# FPGA_Power.net
KiCad netlist of a schematic drawn in Altium Designer
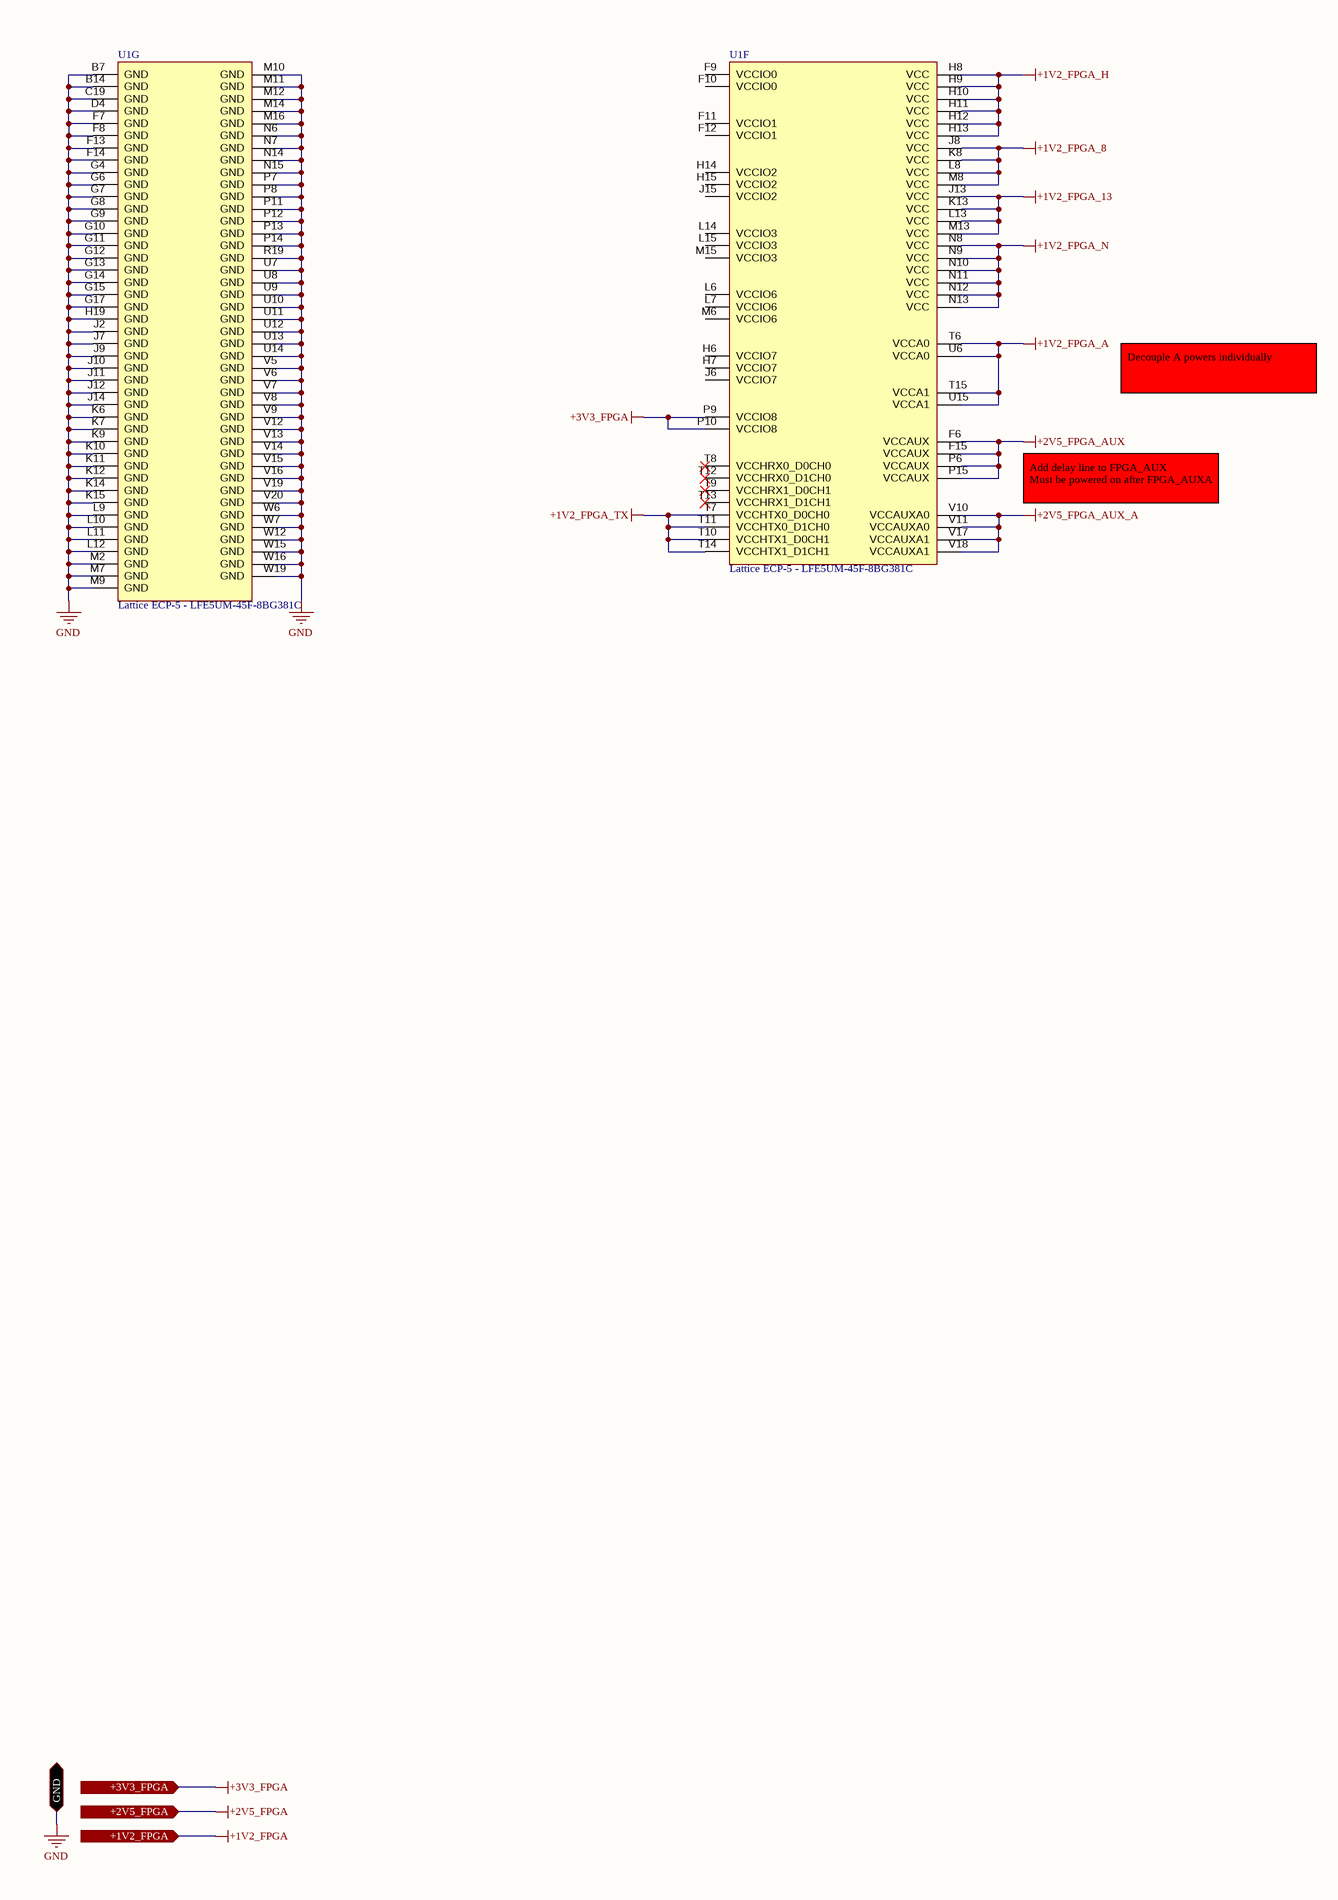
[diagram p0: FPGA Power.SchDoc, left]
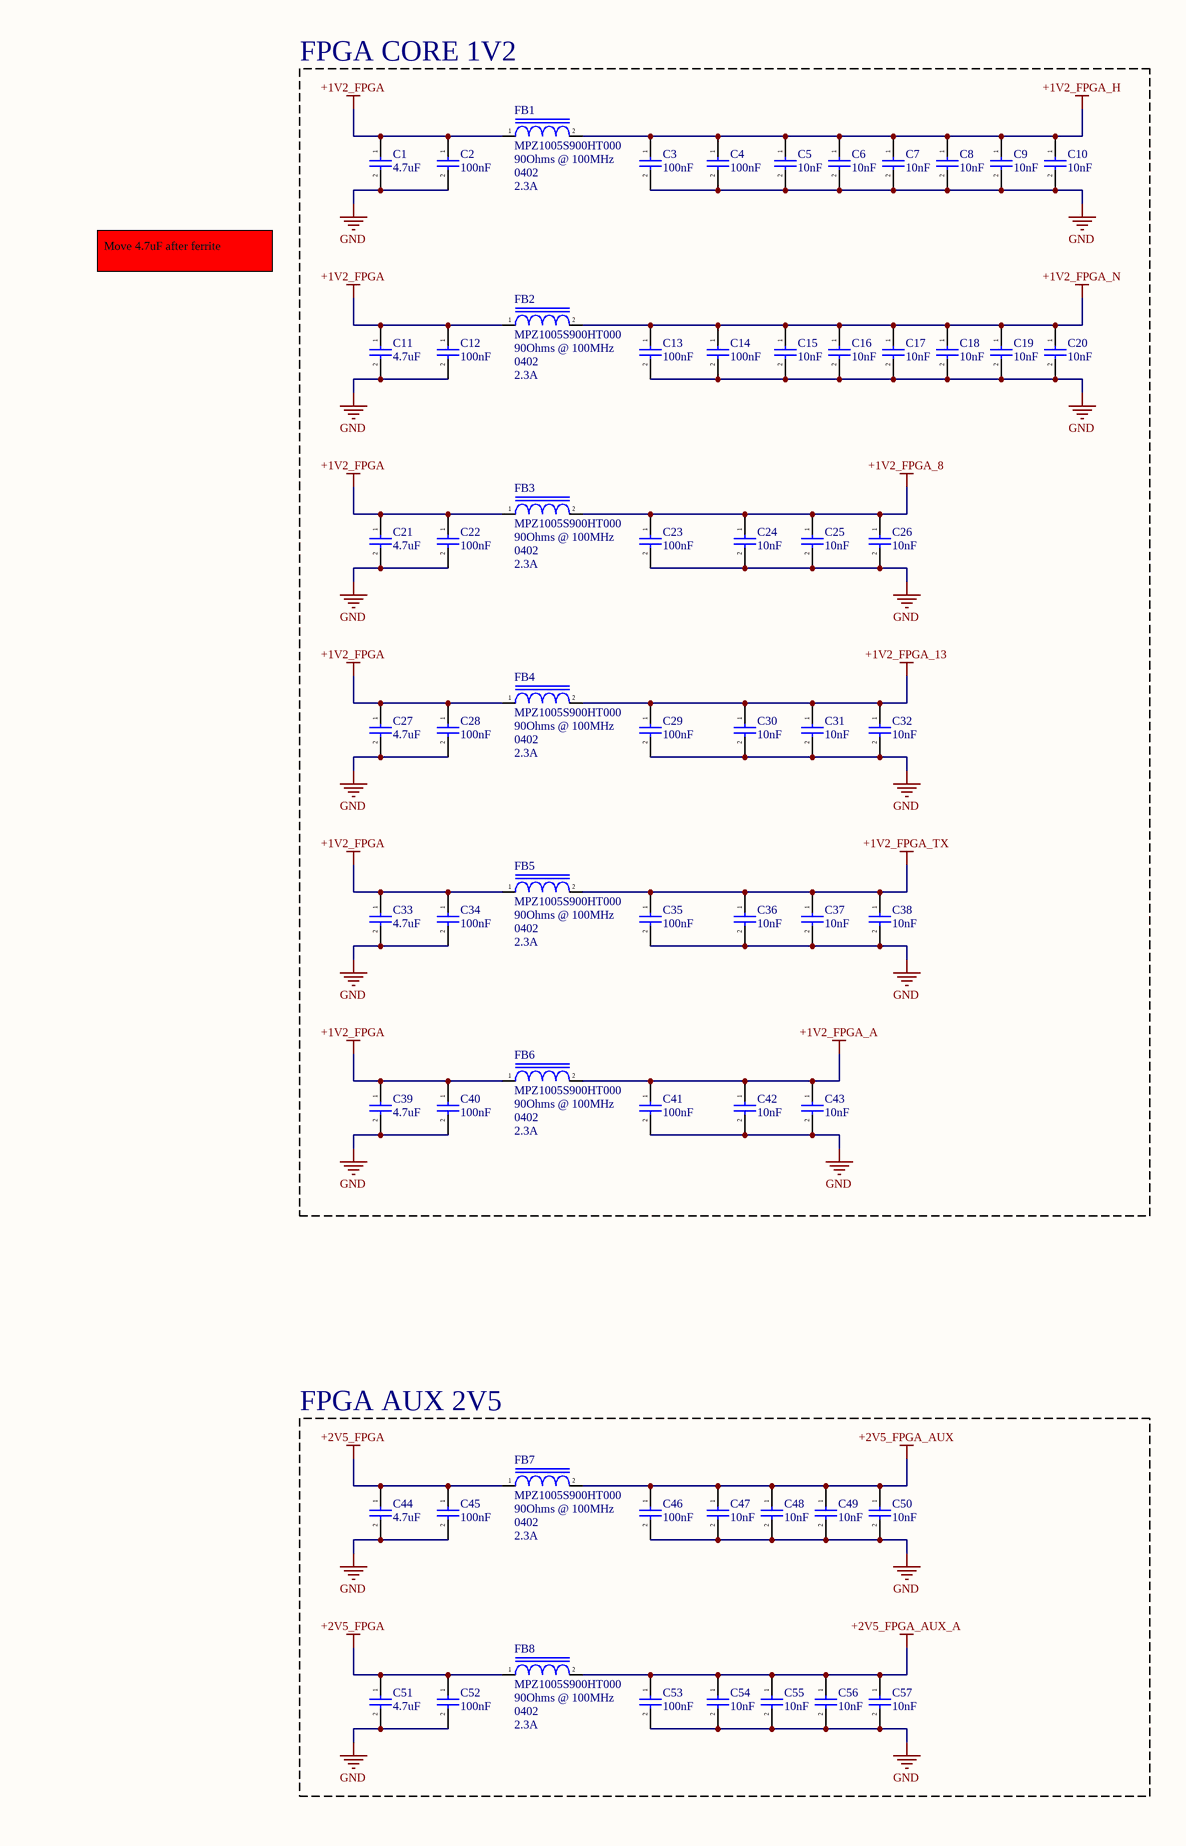
[diagram p1: FPGA Power.SchDoc, right]

(export (version "E")
  (design (tool "Eeschema 10.0.6"))
  (components
    (comp (ref "C1")
      (value "4.7uF")
      (footprint "CAP_0805")
      (description "Generic SMT Ceramic Capacitor")
      (libsource (lib "Symbols") (part "CAP_CER"))
    )
    (comp (ref "C2")
      (value "100nF")
      (footprint "CAP_0402")
      (description "Generic SMT Ceramic Capacitor")
      (libsource (lib "Symbols") (part "CAP_CER"))
    )
    (comp (ref "C3")
      (value "100nF")
      (footprint "CAP_0402")
      (description "Generic SMT Ceramic Capacitor")
      (libsource (lib "Symbols") (part "CAP_CER"))
    )
    (comp (ref "C4")
      (value "100nF")
      (footprint "CAP_0402")
      (description "Generic SMT Ceramic Capacitor")
      (libsource (lib "Symbols") (part "CAP_CER"))
    )
    (comp (ref "C5")
      (value "10nF")
      (footprint "CAP_0201")
      (description "Generic SMT Ceramic Capacitor")
      (libsource (lib "Symbols") (part "CAP_CER"))
    )
    (comp (ref "C6")
      (value "10nF")
      (footprint "CAP_0201")
      (description "Generic SMT Ceramic Capacitor")
      (libsource (lib "Symbols") (part "CAP_CER"))
    )
    (comp (ref "C7")
      (value "10nF")
      (footprint "CAP_0201")
      (description "Generic SMT Ceramic Capacitor")
      (libsource (lib "Symbols") (part "CAP_CER"))
    )
    (comp (ref "C8")
      (value "10nF")
      (footprint "CAP_0201")
      (description "Generic SMT Ceramic Capacitor")
      (libsource (lib "Symbols") (part "CAP_CER"))
    )
    (comp (ref "C9")
      (value "10nF")
      (footprint "CAP_0201")
      (description "Generic SMT Ceramic Capacitor")
      (libsource (lib "Symbols") (part "CAP_CER"))
    )
    (comp (ref "C10")
      (value "10nF")
      (footprint "CAP_0201")
      (description "Generic SMT Ceramic Capacitor")
      (libsource (lib "Symbols") (part "CAP_CER"))
    )
    (comp (ref "C11")
      (value "4.7uF")
      (footprint "CAP_0805")
      (description "Generic SMT Ceramic Capacitor")
      (libsource (lib "Symbols") (part "CAP_CER"))
    )
    (comp (ref "C12")
      (value "100nF")
      (footprint "CAP_0402")
      (description "Generic SMT Ceramic Capacitor")
      (libsource (lib "Symbols") (part "CAP_CER"))
    )
    (comp (ref "C13")
      (value "100nF")
      (footprint "CAP_0402")
      (description "Generic SMT Ceramic Capacitor")
      (libsource (lib "Symbols") (part "CAP_CER"))
    )
    (comp (ref "C14")
      (value "100nF")
      (footprint "CAP_0402")
      (description "Generic SMT Ceramic Capacitor")
      (libsource (lib "Symbols") (part "CAP_CER"))
    )
    (comp (ref "C15")
      (value "10nF")
      (footprint "CAP_0201")
      (description "Generic SMT Ceramic Capacitor")
      (libsource (lib "Symbols") (part "CAP_CER"))
    )
    (comp (ref "C16")
      (value "10nF")
      (footprint "CAP_0201")
      (description "Generic SMT Ceramic Capacitor")
      (libsource (lib "Symbols") (part "CAP_CER"))
    )
    (comp (ref "C17")
      (value "10nF")
      (footprint "CAP_0201")
      (description "Generic SMT Ceramic Capacitor")
      (libsource (lib "Symbols") (part "CAP_CER"))
    )
    (comp (ref "C18")
      (value "10nF")
      (footprint "CAP_0201")
      (description "Generic SMT Ceramic Capacitor")
      (libsource (lib "Symbols") (part "CAP_CER"))
    )
    (comp (ref "C19")
      (value "10nF")
      (footprint "CAP_0201")
      (description "Generic SMT Ceramic Capacitor")
      (libsource (lib "Symbols") (part "CAP_CER"))
    )
    (comp (ref "C20")
      (value "10nF")
      (footprint "CAP_0201")
      (description "Generic SMT Ceramic Capacitor")
      (libsource (lib "Symbols") (part "CAP_CER"))
    )
    (comp (ref "C21")
      (value "4.7uF")
      (footprint "CAP_0805")
      (description "Generic SMT Ceramic Capacitor")
      (libsource (lib "Symbols") (part "CAP_CER"))
    )
    (comp (ref "C22")
      (value "100nF")
      (footprint "CAP_0402")
      (description "Generic SMT Ceramic Capacitor")
      (libsource (lib "Symbols") (part "CAP_CER"))
    )
    (comp (ref "C23")
      (value "100nF")
      (footprint "CAP_0402")
      (description "Generic SMT Ceramic Capacitor")
      (libsource (lib "Symbols") (part "CAP_CER"))
    )
    (comp (ref "C24")
      (value "10nF")
      (footprint "CAP_0201")
      (description "Generic SMT Ceramic Capacitor")
      (libsource (lib "Symbols") (part "CAP_CER"))
    )
    (comp (ref "C25")
      (value "10nF")
      (footprint "CAP_0201")
      (description "Generic SMT Ceramic Capacitor")
      (libsource (lib "Symbols") (part "CAP_CER"))
    )
    (comp (ref "C26")
      (value "10nF")
      (footprint "CAP_0201")
      (description "Generic SMT Ceramic Capacitor")
      (libsource (lib "Symbols") (part "CAP_CER"))
    )
    (comp (ref "C27")
      (value "4.7uF")
      (footprint "CAP_0805")
      (description "Generic SMT Ceramic Capacitor")
      (libsource (lib "Symbols") (part "CAP_CER"))
    )
    (comp (ref "C28")
      (value "100nF")
      (footprint "CAP_0402")
      (description "Generic SMT Ceramic Capacitor")
      (libsource (lib "Symbols") (part "CAP_CER"))
    )
    (comp (ref "C29")
      (value "100nF")
      (footprint "CAP_0402")
      (description "Generic SMT Ceramic Capacitor")
      (libsource (lib "Symbols") (part "CAP_CER"))
    )
    (comp (ref "C30")
      (value "10nF")
      (footprint "CAP_0201")
      (description "Generic SMT Ceramic Capacitor")
      (libsource (lib "Symbols") (part "CAP_CER"))
    )
    (comp (ref "C31")
      (value "10nF")
      (footprint "CAP_0201")
      (description "Generic SMT Ceramic Capacitor")
      (libsource (lib "Symbols") (part "CAP_CER"))
    )
    (comp (ref "C32")
      (value "10nF")
      (footprint "CAP_0201")
      (description "Generic SMT Ceramic Capacitor")
      (libsource (lib "Symbols") (part "CAP_CER"))
    )
    (comp (ref "C33")
      (value "4.7uF")
      (footprint "CAP_0805")
      (description "Generic SMT Ceramic Capacitor")
      (libsource (lib "Symbols") (part "CAP_CER"))
    )
    (comp (ref "C34")
      (value "100nF")
      (footprint "CAP_0402")
      (description "Generic SMT Ceramic Capacitor")
      (libsource (lib "Symbols") (part "CAP_CER"))
    )
    (comp (ref "C35")
      (value "100nF")
      (footprint "CAP_0402")
      (description "Generic SMT Ceramic Capacitor")
      (libsource (lib "Symbols") (part "CAP_CER"))
    )
    (comp (ref "C36")
      (value "10nF")
      (footprint "CAP_0201")
      (description "Generic SMT Ceramic Capacitor")
      (libsource (lib "Symbols") (part "CAP_CER"))
    )
    (comp (ref "C37")
      (value "10nF")
      (footprint "CAP_0201")
      (description "Generic SMT Ceramic Capacitor")
      (libsource (lib "Symbols") (part "CAP_CER"))
    )
    (comp (ref "C38")
      (value "10nF")
      (footprint "CAP_0201")
      (description "Generic SMT Ceramic Capacitor")
      (libsource (lib "Symbols") (part "CAP_CER"))
    )
    (comp (ref "C39")
      (value "4.7uF")
      (footprint "CAP_0805")
      (description "Generic SMT Ceramic Capacitor")
      (libsource (lib "Symbols") (part "CAP_CER"))
    )
    (comp (ref "C40")
      (value "100nF")
      (footprint "CAP_0402")
      (description "Generic SMT Ceramic Capacitor")
      (libsource (lib "Symbols") (part "CAP_CER"))
    )
    (comp (ref "C41")
      (value "100nF")
      (footprint "CAP_0402")
      (description "Generic SMT Ceramic Capacitor")
      (libsource (lib "Symbols") (part "CAP_CER"))
    )
    (comp (ref "C42")
      (value "10nF")
      (footprint "CAP_0201")
      (description "Generic SMT Ceramic Capacitor")
      (libsource (lib "Symbols") (part "CAP_CER"))
    )
    (comp (ref "C43")
      (value "10nF")
      (footprint "CAP_0201")
      (description "Generic SMT Ceramic Capacitor")
      (libsource (lib "Symbols") (part "CAP_CER"))
    )
    (comp (ref "C44")
      (value "4.7uF")
      (footprint "CAP_0805")
      (description "Generic SMT Ceramic Capacitor")
      (libsource (lib "Symbols") (part "CAP_CER"))
    )
    (comp (ref "C45")
      (value "100nF")
      (footprint "CAP_0402")
      (description "Generic SMT Ceramic Capacitor")
      (libsource (lib "Symbols") (part "CAP_CER"))
    )
    (comp (ref "C46")
      (value "100nF")
      (footprint "CAP_0402")
      (description "Generic SMT Ceramic Capacitor")
      (libsource (lib "Symbols") (part "CAP_CER"))
    )
    (comp (ref "C47")
      (value "10nF")
      (footprint "CAP_0201")
      (description "Generic SMT Ceramic Capacitor")
      (libsource (lib "Symbols") (part "CAP_CER"))
    )
    (comp (ref "C48")
      (value "10nF")
      (footprint "CAP_0201")
      (description "Generic SMT Ceramic Capacitor")
      (libsource (lib "Symbols") (part "CAP_CER"))
    )
    (comp (ref "C49")
      (value "10nF")
      (footprint "CAP_0201")
      (description "Generic SMT Ceramic Capacitor")
      (libsource (lib "Symbols") (part "CAP_CER"))
    )
    (comp (ref "C50")
      (value "10nF")
      (footprint "CAP_0201")
      (description "Generic SMT Ceramic Capacitor")
      (libsource (lib "Symbols") (part "CAP_CER"))
    )
    (comp (ref "C51")
      (value "4.7uF")
      (footprint "CAP_0805")
      (description "Generic SMT Ceramic Capacitor")
      (libsource (lib "Symbols") (part "CAP_CER"))
    )
    (comp (ref "C52")
      (value "100nF")
      (footprint "CAP_0402")
      (description "Generic SMT Ceramic Capacitor")
      (libsource (lib "Symbols") (part "CAP_CER"))
    )
    (comp (ref "C53")
      (value "100nF")
      (footprint "CAP_0402")
      (description "Generic SMT Ceramic Capacitor")
      (libsource (lib "Symbols") (part "CAP_CER"))
    )
    (comp (ref "C54")
      (value "10nF")
      (footprint "CAP_0201")
      (description "Generic SMT Ceramic Capacitor")
      (libsource (lib "Symbols") (part "CAP_CER"))
    )
    (comp (ref "C55")
      (value "10nF")
      (footprint "CAP_0201")
      (description "Generic SMT Ceramic Capacitor")
      (libsource (lib "Symbols") (part "CAP_CER"))
    )
    (comp (ref "C56")
      (value "10nF")
      (footprint "CAP_0201")
      (description "Generic SMT Ceramic Capacitor")
      (libsource (lib "Symbols") (part "CAP_CER"))
    )
    (comp (ref "C57")
      (value "10nF")
      (footprint "CAP_0201")
      (description "Generic SMT Ceramic Capacitor")
      (libsource (lib "Symbols") (part "CAP_CER"))
    )
    (comp (ref "FB1")
      (value "MPZ1005S900HT000")
      (footprint "IND_0402")
      (description "90 Ohms @ 100 MHz 1 Power Line Ferrite Bead 0402 (1005 Metric) 2.3A 38mOhm")
      (fields
        (field (name "IMPEDANCE @ FREQ") "90Ohms @ 100MHz")
        (field (name "PACKAGE / CASE") "0402")
        (field (name "CURRENT RATING") "2.3A")
      )
      (libsource (lib "CryptLib") (part "IND_MPZ1005S900HT000"))
    )
    (comp (ref "FB2")
      (value "MPZ1005S900HT000")
      (footprint "IND_0402")
      (description "90 Ohms @ 100 MHz 1 Power Line Ferrite Bead 0402 (1005 Metric) 2.3A 38mOhm")
      (fields
        (field (name "IMPEDANCE @ FREQ") "90Ohms @ 100MHz")
        (field (name "PACKAGE / CASE") "0402")
        (field (name "CURRENT RATING") "2.3A")
      )
      (libsource (lib "CryptLib") (part "IND_MPZ1005S900HT000"))
    )
    (comp (ref "FB3")
      (value "MPZ1005S900HT000")
      (footprint "IND_0402")
      (description "90 Ohms @ 100 MHz 1 Power Line Ferrite Bead 0402 (1005 Metric) 2.3A 38mOhm")
      (fields
        (field (name "IMPEDANCE @ FREQ") "90Ohms @ 100MHz")
        (field (name "PACKAGE / CASE") "0402")
        (field (name "CURRENT RATING") "2.3A")
      )
      (libsource (lib "CryptLib") (part "IND_MPZ1005S900HT000"))
    )
    (comp (ref "FB4")
      (value "MPZ1005S900HT000")
      (footprint "IND_0402")
      (description "90 Ohms @ 100 MHz 1 Power Line Ferrite Bead 0402 (1005 Metric) 2.3A 38mOhm")
      (fields
        (field (name "IMPEDANCE @ FREQ") "90Ohms @ 100MHz")
        (field (name "PACKAGE / CASE") "0402")
        (field (name "CURRENT RATING") "2.3A")
      )
      (libsource (lib "CryptLib") (part "IND_MPZ1005S900HT000"))
    )
    (comp (ref "FB5")
      (value "MPZ1005S900HT000")
      (footprint "IND_0402")
      (description "90 Ohms @ 100 MHz 1 Power Line Ferrite Bead 0402 (1005 Metric) 2.3A 38mOhm")
      (fields
        (field (name "IMPEDANCE @ FREQ") "90Ohms @ 100MHz")
        (field (name "PACKAGE / CASE") "0402")
        (field (name "CURRENT RATING") "2.3A")
      )
      (libsource (lib "CryptLib") (part "IND_MPZ1005S900HT000"))
    )
    (comp (ref "FB6")
      (value "MPZ1005S900HT000")
      (footprint "IND_0402")
      (description "90 Ohms @ 100 MHz 1 Power Line Ferrite Bead 0402 (1005 Metric) 2.3A 38mOhm")
      (fields
        (field (name "IMPEDANCE @ FREQ") "90Ohms @ 100MHz")
        (field (name "PACKAGE / CASE") "0402")
        (field (name "CURRENT RATING") "2.3A")
      )
      (libsource (lib "CryptLib") (part "IND_MPZ1005S900HT000"))
    )
    (comp (ref "FB7")
      (value "MPZ1005S900HT000")
      (footprint "IND_0402")
      (description "90 Ohms @ 100 MHz 1 Power Line Ferrite Bead 0402 (1005 Metric) 2.3A 38mOhm")
      (fields
        (field (name "IMPEDANCE @ FREQ") "90Ohms @ 100MHz")
        (field (name "PACKAGE / CASE") "0402")
        (field (name "CURRENT RATING") "2.3A")
      )
      (libsource (lib "CryptLib") (part "IND_MPZ1005S900HT000"))
    )
    (comp (ref "FB8")
      (value "MPZ1005S900HT000")
      (footprint "IND_0402")
      (description "90 Ohms @ 100 MHz 1 Power Line Ferrite Bead 0402 (1005 Metric) 2.3A 38mOhm")
      (fields
        (field (name "IMPEDANCE @ FREQ") "90Ohms @ 100MHz")
        (field (name "PACKAGE / CASE") "0402")
        (field (name "CURRENT RATING") "2.3A")
      )
      (libsource (lib "CryptLib") (part "IND_MPZ1005S900HT000"))
    )
    (comp (ref "U1")
      (value "Lattice ECP-5 - LFE5UM-45F-8BG381C")
      (footprint "CryptLib:CABGA-381")
      (description "IC FPGA 203 I/O 381CABGA")
      (fields (field (name "MFR") "Lattice Semiconductors"))
      (libsource (lib "CryptLib") (part "IC_LFE5UM-45F-8BG381C"))
    )
  )
  (nets
    (net (code "1") (name "+1V2_FPGA") (class "Default")
      (node (ref "C1") (pin "1") (pinfunction "1_1") (pintype "passive"))
      (node (ref "C11") (pin "1") (pinfunction "1_1") (pintype "passive"))
      (node (ref "C12") (pin "1") (pinfunction "1_1") (pintype "passive"))
      (node (ref "C2") (pin "1") (pinfunction "1_1") (pintype "passive"))
      (node (ref "C21") (pin "1") (pinfunction "1_1") (pintype "passive"))
      (node (ref "C22") (pin "1") (pinfunction "1_1") (pintype "passive"))
      (node (ref "C27") (pin "1") (pinfunction "1_1") (pintype "passive"))
      (node (ref "C28") (pin "1") (pinfunction "1_1") (pintype "passive"))
      (node (ref "C33") (pin "1") (pinfunction "1_1") (pintype "passive"))
      (node (ref "C34") (pin "1") (pinfunction "1_1") (pintype "passive"))
      (node (ref "C39") (pin "1") (pinfunction "1_1") (pintype "passive"))
      (node (ref "C40") (pin "1") (pinfunction "1_1") (pintype "passive"))
      (node (ref "FB1") (pin "1") (pinfunction "1_1") (pintype "passive"))
      (node (ref "FB2") (pin "1") (pinfunction "1_1") (pintype "passive"))
      (node (ref "FB3") (pin "1") (pinfunction "1_1") (pintype "passive"))
      (node (ref "FB4") (pin "1") (pinfunction "1_1") (pintype "passive"))
      (node (ref "FB5") (pin "1") (pinfunction "1_1") (pintype "passive"))
      (node (ref "FB6") (pin "1") (pinfunction "1_1") (pintype "passive"))
    )
    (net (code "2") (name "+1V2_FPGA_8") (class "Default")
      (node (ref "C23") (pin "1") (pinfunction "1_1") (pintype "passive"))
      (node (ref "C24") (pin "1") (pinfunction "1_1") (pintype "passive"))
      (node (ref "C25") (pin "1") (pinfunction "1_1") (pintype "passive"))
      (node (ref "C26") (pin "1") (pinfunction "1_1") (pintype "passive"))
      (node (ref "FB3") (pin "2") (pinfunction "2_2") (pintype "passive"))
      (node (ref "U1") (pin "J8") (pinfunction "VCC_J8") (pintype "power_in"))
      (node (ref "U1") (pin "K8") (pinfunction "VCC_K8") (pintype "power_in"))
      (node (ref "U1") (pin "L8") (pinfunction "VCC_L8") (pintype "power_in"))
      (node (ref "U1") (pin "M8") (pinfunction "VCC_M8") (pintype "power_in"))
    )
    (net (code "3") (name "+1V2_FPGA_13") (class "Default")
      (node (ref "C29") (pin "1") (pinfunction "1_1") (pintype "passive"))
      (node (ref "C30") (pin "1") (pinfunction "1_1") (pintype "passive"))
      (node (ref "C31") (pin "1") (pinfunction "1_1") (pintype "passive"))
      (node (ref "C32") (pin "1") (pinfunction "1_1") (pintype "passive"))
      (node (ref "FB4") (pin "2") (pinfunction "2_2") (pintype "passive"))
      (node (ref "U1") (pin "J13") (pinfunction "VCC_J13") (pintype "power_in"))
      (node (ref "U1") (pin "K13") (pinfunction "VCC_K13") (pintype "power_in"))
      (node (ref "U1") (pin "L13") (pinfunction "VCC_L13") (pintype "power_in"))
      (node (ref "U1") (pin "M13") (pinfunction "VCC_M13") (pintype "power_in"))
    )
    (net (code "4") (name "+1V2_FPGA_A") (class "Default")
      (node (ref "C41") (pin "1") (pinfunction "1_1") (pintype "passive"))
      (node (ref "C42") (pin "1") (pinfunction "1_1") (pintype "passive"))
      (node (ref "C43") (pin "1") (pinfunction "1_1") (pintype "passive"))
      (node (ref "FB6") (pin "2") (pinfunction "2_2") (pintype "passive"))
      (node (ref "U1") (pin "T15") (pinfunction "VCCA1_T15") (pintype "power_in"))
      (node (ref "U1") (pin "T6") (pinfunction "VCCA0_T6") (pintype "power_in"))
      (node (ref "U1") (pin "U15") (pinfunction "VCCA1_U15") (pintype "power_in"))
      (node (ref "U1") (pin "U6") (pinfunction "VCCA0_U6") (pintype "power_in"))
    )
    (net (code "5") (name "+1V2_FPGA_H") (class "Default")
      (node (ref "C10") (pin "1") (pinfunction "1_1") (pintype "passive"))
      (node (ref "C3") (pin "1") (pinfunction "1_1") (pintype "passive"))
      (node (ref "C4") (pin "1") (pinfunction "1_1") (pintype "passive"))
      (node (ref "C5") (pin "1") (pinfunction "1_1") (pintype "passive"))
      (node (ref "C6") (pin "1") (pinfunction "1_1") (pintype "passive"))
      (node (ref "C7") (pin "1") (pinfunction "1_1") (pintype "passive"))
      (node (ref "C8") (pin "1") (pinfunction "1_1") (pintype "passive"))
      (node (ref "C9") (pin "1") (pinfunction "1_1") (pintype "passive"))
      (node (ref "FB1") (pin "2") (pinfunction "2_2") (pintype "passive"))
      (node (ref "U1") (pin "H10") (pinfunction "VCC_H10") (pintype "power_in"))
      (node (ref "U1") (pin "H11") (pinfunction "VCC_H11") (pintype "power_in"))
      (node (ref "U1") (pin "H12") (pinfunction "VCC_H12") (pintype "power_in"))
      (node (ref "U1") (pin "H13") (pinfunction "VCC_H13") (pintype "power_in"))
      (node (ref "U1") (pin "H8") (pinfunction "VCC_H8") (pintype "power_in"))
      (node (ref "U1") (pin "H9") (pinfunction "VCC_H9") (pintype "power_in"))
    )
    (net (code "6") (name "+1V2_FPGA_N") (class "Default")
      (node (ref "C13") (pin "1") (pinfunction "1_1") (pintype "passive"))
      (node (ref "C14") (pin "1") (pinfunction "1_1") (pintype "passive"))
      (node (ref "C15") (pin "1") (pinfunction "1_1") (pintype "passive"))
      (node (ref "C16") (pin "1") (pinfunction "1_1") (pintype "passive"))
      (node (ref "C17") (pin "1") (pinfunction "1_1") (pintype "passive"))
      (node (ref "C18") (pin "1") (pinfunction "1_1") (pintype "passive"))
      (node (ref "C19") (pin "1") (pinfunction "1_1") (pintype "passive"))
      (node (ref "C20") (pin "1") (pinfunction "1_1") (pintype "passive"))
      (node (ref "FB2") (pin "2") (pinfunction "2_2") (pintype "passive"))
      (node (ref "U1") (pin "N10") (pinfunction "VCC_N10") (pintype "power_in"))
      (node (ref "U1") (pin "N11") (pinfunction "VCC_N11") (pintype "power_in"))
      (node (ref "U1") (pin "N12") (pinfunction "VCC_N12") (pintype "power_in"))
      (node (ref "U1") (pin "N13") (pinfunction "VCC_N13") (pintype "power_in"))
      (node (ref "U1") (pin "N8") (pinfunction "VCC_N8") (pintype "power_in"))
      (node (ref "U1") (pin "N9") (pinfunction "VCC_N9") (pintype "power_in"))
    )
    (net (code "7") (name "+1V2_FPGA_TX") (class "Default")
      (node (ref "C35") (pin "1") (pinfunction "1_1") (pintype "passive"))
      (node (ref "C36") (pin "1") (pinfunction "1_1") (pintype "passive"))
      (node (ref "C37") (pin "1") (pinfunction "1_1") (pintype "passive"))
      (node (ref "C38") (pin "1") (pinfunction "1_1") (pintype "passive"))
      (node (ref "FB5") (pin "2") (pinfunction "2_2") (pintype "passive"))
      (node (ref "U1") (pin "T10") (pinfunction "VCCHTX1_D0CH1_T10") (pintype "power_in"))
      (node (ref "U1") (pin "T11") (pinfunction "VCCHTX0_D1CH0_T11") (pintype "power_in"))
      (node (ref "U1") (pin "T14") (pinfunction "VCCHTX1_D1CH1_T14") (pintype "power_in"))
      (node (ref "U1") (pin "T7") (pinfunction "VCCHTX0_D0CH0_T7") (pintype "power_in"))
    )
    (net (code "8") (name "+2V5_FPGA") (class "Default")
      (node (ref "C44") (pin "1") (pinfunction "1_1") (pintype "passive"))
      (node (ref "C45") (pin "1") (pinfunction "1_1") (pintype "passive"))
      (node (ref "C51") (pin "1") (pinfunction "1_1") (pintype "passive"))
      (node (ref "C52") (pin "1") (pinfunction "1_1") (pintype "passive"))
      (node (ref "FB7") (pin "1") (pinfunction "1_1") (pintype "passive"))
      (node (ref "FB8") (pin "1") (pinfunction "1_1") (pintype "passive"))
    )
    (net (code "9") (name "+2V5_FPGA_AUX") (class "Default")
      (node (ref "C46") (pin "1") (pinfunction "1_1") (pintype "passive"))
      (node (ref "C47") (pin "1") (pinfunction "1_1") (pintype "passive"))
      (node (ref "C48") (pin "1") (pinfunction "1_1") (pintype "passive"))
      (node (ref "C49") (pin "1") (pinfunction "1_1") (pintype "passive"))
      (node (ref "C50") (pin "1") (pinfunction "1_1") (pintype "passive"))
      (node (ref "FB7") (pin "2") (pinfunction "2_2") (pintype "passive"))
      (node (ref "U1") (pin "F15") (pinfunction "VCCAUX_F15") (pintype "power_in"))
      (node (ref "U1") (pin "F6") (pinfunction "VCCAUX_F6") (pintype "power_in"))
      (node (ref "U1") (pin "P15") (pinfunction "VCCAUX_P15") (pintype "power_in"))
      (node (ref "U1") (pin "P6") (pinfunction "VCCAUX_P6") (pintype "power_in"))
    )
    (net (code "10") (name "+2V5_FPGA_AUX_A") (class "Default")
      (node (ref "C53") (pin "1") (pinfunction "1_1") (pintype "passive"))
      (node (ref "C54") (pin "1") (pinfunction "1_1") (pintype "passive"))
      (node (ref "C55") (pin "1") (pinfunction "1_1") (pintype "passive"))
      (node (ref "C56") (pin "1") (pinfunction "1_1") (pintype "passive"))
      (node (ref "C57") (pin "1") (pinfunction "1_1") (pintype "passive"))
      (node (ref "FB8") (pin "2") (pinfunction "2_2") (pintype "passive"))
      (node (ref "U1") (pin "V10") (pinfunction "VCCAUXA0_V10") (pintype "power_in"))
      (node (ref "U1") (pin "V11") (pinfunction "VCCAUXA0_V11") (pintype "power_in"))
      (node (ref "U1") (pin "V17") (pinfunction "VCCAUXA1_V17") (pintype "power_in"))
      (node (ref "U1") (pin "V18") (pinfunction "VCCAUXA1_V18") (pintype "power_in"))
    )
    (net (code "11") (name "+3V3_FPGA") (class "Default")
      (node (ref "U1") (pin "P10") (pinfunction "VCCIO8_P10") (pintype "power_in"))
      (node (ref "U1") (pin "P9") (pinfunction "VCCIO8_P9") (pintype "power_in"))
    )
    (net (code "12") (name "GND") (class "Default")
      (node (ref "C1") (pin "2") (pinfunction "2_2") (pintype "passive"))
      (node (ref "C10") (pin "2") (pinfunction "2_2") (pintype "passive"))
      (node (ref "C11") (pin "2") (pinfunction "2_2") (pintype "passive"))
      (node (ref "C12") (pin "2") (pinfunction "2_2") (pintype "passive"))
      (node (ref "C13") (pin "2") (pinfunction "2_2") (pintype "passive"))
      (node (ref "C14") (pin "2") (pinfunction "2_2") (pintype "passive"))
      (node (ref "C15") (pin "2") (pinfunction "2_2") (pintype "passive"))
      (node (ref "C16") (pin "2") (pinfunction "2_2") (pintype "passive"))
      (node (ref "C17") (pin "2") (pinfunction "2_2") (pintype "passive"))
      (node (ref "C18") (pin "2") (pinfunction "2_2") (pintype "passive"))
      (node (ref "C19") (pin "2") (pinfunction "2_2") (pintype "passive"))
      (node (ref "C2") (pin "2") (pinfunction "2_2") (pintype "passive"))
      (node (ref "C20") (pin "2") (pinfunction "2_2") (pintype "passive"))
      (node (ref "C21") (pin "2") (pinfunction "2_2") (pintype "passive"))
      (node (ref "C22") (pin "2") (pinfunction "2_2") (pintype "passive"))
      (node (ref "C23") (pin "2") (pinfunction "2_2") (pintype "passive"))
      (node (ref "C24") (pin "2") (pinfunction "2_2") (pintype "passive"))
      (node (ref "C25") (pin "2") (pinfunction "2_2") (pintype "passive"))
      (node (ref "C26") (pin "2") (pinfunction "2_2") (pintype "passive"))
      (node (ref "C27") (pin "2") (pinfunction "2_2") (pintype "passive"))
      (node (ref "C28") (pin "2") (pinfunction "2_2") (pintype "passive"))
      (node (ref "C29") (pin "2") (pinfunction "2_2") (pintype "passive"))
      (node (ref "C3") (pin "2") (pinfunction "2_2") (pintype "passive"))
      (node (ref "C30") (pin "2") (pinfunction "2_2") (pintype "passive"))
      (node (ref "C31") (pin "2") (pinfunction "2_2") (pintype "passive"))
      (node (ref "C32") (pin "2") (pinfunction "2_2") (pintype "passive"))
      (node (ref "C33") (pin "2") (pinfunction "2_2") (pintype "passive"))
      (node (ref "C34") (pin "2") (pinfunction "2_2") (pintype "passive"))
      (node (ref "C35") (pin "2") (pinfunction "2_2") (pintype "passive"))
      (node (ref "C36") (pin "2") (pinfunction "2_2") (pintype "passive"))
      (node (ref "C37") (pin "2") (pinfunction "2_2") (pintype "passive"))
      (node (ref "C38") (pin "2") (pinfunction "2_2") (pintype "passive"))
      (node (ref "C39") (pin "2") (pinfunction "2_2") (pintype "passive"))
      (node (ref "C4") (pin "2") (pinfunction "2_2") (pintype "passive"))
      (node (ref "C40") (pin "2") (pinfunction "2_2") (pintype "passive"))
      (node (ref "C41") (pin "2") (pinfunction "2_2") (pintype "passive"))
      (node (ref "C42") (pin "2") (pinfunction "2_2") (pintype "passive"))
      (node (ref "C43") (pin "2") (pinfunction "2_2") (pintype "passive"))
      (node (ref "C44") (pin "2") (pinfunction "2_2") (pintype "passive"))
      (node (ref "C45") (pin "2") (pinfunction "2_2") (pintype "passive"))
      (node (ref "C46") (pin "2") (pinfunction "2_2") (pintype "passive"))
      (node (ref "C47") (pin "2") (pinfunction "2_2") (pintype "passive"))
      (node (ref "C48") (pin "2") (pinfunction "2_2") (pintype "passive"))
      (node (ref "C49") (pin "2") (pinfunction "2_2") (pintype "passive"))
      (node (ref "C5") (pin "2") (pinfunction "2_2") (pintype "passive"))
      (node (ref "C50") (pin "2") (pinfunction "2_2") (pintype "passive"))
      (node (ref "C51") (pin "2") (pinfunction "2_2") (pintype "passive"))
      (node (ref "C52") (pin "2") (pinfunction "2_2") (pintype "passive"))
      (node (ref "C53") (pin "2") (pinfunction "2_2") (pintype "passive"))
      (node (ref "C54") (pin "2") (pinfunction "2_2") (pintype "passive"))
      (node (ref "C55") (pin "2") (pinfunction "2_2") (pintype "passive"))
      (node (ref "C56") (pin "2") (pinfunction "2_2") (pintype "passive"))
      (node (ref "C57") (pin "2") (pinfunction "2_2") (pintype "passive"))
      (node (ref "C6") (pin "2") (pinfunction "2_2") (pintype "passive"))
      (node (ref "C7") (pin "2") (pinfunction "2_2") (pintype "passive"))
      (node (ref "C8") (pin "2") (pinfunction "2_2") (pintype "passive"))
      (node (ref "C9") (pin "2") (pinfunction "2_2") (pintype "passive"))
      (node (ref "U1") (pin "B14") (pinfunction "GND_B14") (pintype "power_in"))
      (node (ref "U1") (pin "B7") (pinfunction "GND_B7") (pintype "power_in"))
      (node (ref "U1") (pin "C19") (pinfunction "GND_C19") (pintype "power_in"))
      (node (ref "U1") (pin "D4") (pinfunction "GND_D4") (pintype "power_in"))
      (node (ref "U1") (pin "F13") (pinfunction "GND_F13") (pintype "power_in"))
      (node (ref "U1") (pin "F14") (pinfunction "GND_F14") (pintype "power_in"))
      (node (ref "U1") (pin "F7") (pinfunction "GND_F7") (pintype "power_in"))
      (node (ref "U1") (pin "F8") (pinfunction "GND_F8") (pintype "power_in"))
      (node (ref "U1") (pin "G10") (pinfunction "GND_G10") (pintype "power_in"))
      (node (ref "U1") (pin "G11") (pinfunction "GND_G11") (pintype "power_in"))
      (node (ref "U1") (pin "G12") (pinfunction "GND_G12") (pintype "power_in"))
      (node (ref "U1") (pin "G13") (pinfunction "GND_G13") (pintype "power_in"))
      (node (ref "U1") (pin "G14") (pinfunction "GND_G14") (pintype "power_in"))
      (node (ref "U1") (pin "G15") (pinfunction "GND_G15") (pintype "power_in"))
      (node (ref "U1") (pin "G17") (pinfunction "GND_G17") (pintype "power_in"))
      (node (ref "U1") (pin "G4") (pinfunction "GND_G4") (pintype "power_in"))
      (node (ref "U1") (pin "G6") (pinfunction "GND_G6") (pintype "power_in"))
      (node (ref "U1") (pin "G7") (pinfunction "GND_G7") (pintype "power_in"))
      (node (ref "U1") (pin "G8") (pinfunction "GND_G8") (pintype "power_in"))
      (node (ref "U1") (pin "G9") (pinfunction "GND_G9") (pintype "power_in"))
      (node (ref "U1") (pin "H19") (pinfunction "GND_H19") (pintype "power_in"))
      (node (ref "U1") (pin "J10") (pinfunction "GND_J10") (pintype "power_in"))
      (node (ref "U1") (pin "J11") (pinfunction "GND_J11") (pintype "power_in"))
      (node (ref "U1") (pin "J12") (pinfunction "GND_J12") (pintype "power_in"))
      (node (ref "U1") (pin "J14") (pinfunction "GND_J14") (pintype "power_in"))
      (node (ref "U1") (pin "J2") (pinfunction "GND_J2") (pintype "power_in"))
      (node (ref "U1") (pin "J7") (pinfunction "GND_J7") (pintype "power_in"))
      (node (ref "U1") (pin "J9") (pinfunction "GND_J9") (pintype "power_in"))
      (node (ref "U1") (pin "K10") (pinfunction "GND_K10") (pintype "power_in"))
      (node (ref "U1") (pin "K11") (pinfunction "GND_K11") (pintype "power_in"))
      (node (ref "U1") (pin "K12") (pinfunction "GND_K12") (pintype "power_in"))
      (node (ref "U1") (pin "K14") (pinfunction "GND_K14") (pintype "power_in"))
      (node (ref "U1") (pin "K15") (pinfunction "GND_K15") (pintype "power_in"))
      (node (ref "U1") (pin "K6") (pinfunction "GND_K6") (pintype "power_in"))
      (node (ref "U1") (pin "K7") (pinfunction "GND_K7") (pintype "power_in"))
      (node (ref "U1") (pin "K9") (pinfunction "GND_K9") (pintype "power_in"))
      (node (ref "U1") (pin "L10") (pinfunction "GND_L10") (pintype "power_in"))
      (node (ref "U1") (pin "L11") (pinfunction "GND_L11") (pintype "power_in"))
      (node (ref "U1") (pin "L12") (pinfunction "GND_L12") (pintype "power_in"))
      (node (ref "U1") (pin "L9") (pinfunction "GND_L9") (pintype "power_in"))
      (node (ref "U1") (pin "M10") (pinfunction "GND_M10") (pintype "power_in"))
      (node (ref "U1") (pin "M11") (pinfunction "GND_M11") (pintype "power_in"))
      (node (ref "U1") (pin "M12") (pinfunction "GND_M12") (pintype "power_in"))
      (node (ref "U1") (pin "M14") (pinfunction "GND_M14") (pintype "power_in"))
      (node (ref "U1") (pin "M16") (pinfunction "GND_M16") (pintype "power_in"))
      (node (ref "U1") (pin "M2") (pinfunction "GND_M2") (pintype "power_in"))
      (node (ref "U1") (pin "M7") (pinfunction "GND_M7") (pintype "power_in"))
      (node (ref "U1") (pin "M9") (pinfunction "GND_M9") (pintype "power_in"))
      (node (ref "U1") (pin "N14") (pinfunction "GND_N14") (pintype "power_in"))
      (node (ref "U1") (pin "N15") (pinfunction "GND_N15") (pintype "power_in"))
      (node (ref "U1") (pin "N6") (pinfunction "GND_N6") (pintype "power_in"))
      (node (ref "U1") (pin "N7") (pinfunction "GND_N7") (pintype "power_in"))
      (node (ref "U1") (pin "P11") (pinfunction "GND_P11") (pintype "power_in"))
      (node (ref "U1") (pin "P12") (pinfunction "GND_P12") (pintype "power_in"))
      (node (ref "U1") (pin "P13") (pinfunction "GND_P13") (pintype "power_in"))
      (node (ref "U1") (pin "P14") (pinfunction "GND_P14") (pintype "power_in"))
      (node (ref "U1") (pin "P7") (pinfunction "GND_P7") (pintype "power_in"))
      (node (ref "U1") (pin "P8") (pinfunction "GND_P8") (pintype "power_in"))
      (node (ref "U1") (pin "R19") (pinfunction "GND_R19") (pintype "power_in"))
      (node (ref "U1") (pin "U10") (pinfunction "GND_U10") (pintype "power_in"))
      (node (ref "U1") (pin "U11") (pinfunction "GND_U11") (pintype "power_in"))
      (node (ref "U1") (pin "U12") (pinfunction "GND_U12") (pintype "power_in"))
      (node (ref "U1") (pin "U13") (pinfunction "GND_U13") (pintype "power_in"))
      (node (ref "U1") (pin "U14") (pinfunction "GND_U14") (pintype "power_in"))
      (node (ref "U1") (pin "U7") (pinfunction "GND_U7") (pintype "power_in"))
      (node (ref "U1") (pin "U8") (pinfunction "GND_U8") (pintype "power_in"))
      (node (ref "U1") (pin "U9") (pinfunction "GND_U9") (pintype "power_in"))
      (node (ref "U1") (pin "V12") (pinfunction "GND_V12") (pintype "power_in"))
      (node (ref "U1") (pin "V13") (pinfunction "GND_V13") (pintype "power_in"))
      (node (ref "U1") (pin "V14") (pinfunction "GND_V14") (pintype "power_in"))
      (node (ref "U1") (pin "V15") (pinfunction "GND_V15") (pintype "power_in"))
      (node (ref "U1") (pin "V16") (pinfunction "GND_V16") (pintype "power_in"))
      (node (ref "U1") (pin "V19") (pinfunction "GND_V19") (pintype "power_in"))
      (node (ref "U1") (pin "V20") (pinfunction "GND_V20") (pintype "power_in"))
      (node (ref "U1") (pin "V5") (pinfunction "GND_V5") (pintype "power_in"))
      (node (ref "U1") (pin "V6") (pinfunction "GND_V6") (pintype "power_in"))
      (node (ref "U1") (pin "V7") (pinfunction "GND_V7") (pintype "power_in"))
      (node (ref "U1") (pin "V8") (pinfunction "GND_V8") (pintype "power_in"))
      (node (ref "U1") (pin "V9") (pinfunction "GND_V9") (pintype "power_in"))
      (node (ref "U1") (pin "W12") (pinfunction "GND_W12") (pintype "power_in"))
      (node (ref "U1") (pin "W15") (pinfunction "GND_W15") (pintype "power_in"))
      (node (ref "U1") (pin "W16") (pinfunction "GND_W16") (pintype "power_in"))
      (node (ref "U1") (pin "W19") (pinfunction "GND_W19") (pintype "power_in"))
      (node (ref "U1") (pin "W6") (pinfunction "GND_W6") (pintype "power_in"))
      (node (ref "U1") (pin "W7") (pinfunction "GND_W7") (pintype "power_in"))
    )
    (net (code "13") (name "unconnected-(U1F-VCCHRX0_D0CH0-PadT8)") (class "Default")
      (node (ref "U1") (pin "T8") (pinfunction "VCCHRX0_D0CH0_T8") (pintype "power_in+no_connect"))
    )
    (net (code "14") (name "unconnected-(U1F-VCCHRX0_D1CH0-PadT12)") (class "Default")
      (node (ref "U1") (pin "T12") (pinfunction "VCCHRX0_D1CH0_T12") (pintype "power_in+no_connect"))
    )
    (net (code "15") (name "unconnected-(U1F-VCCHRX1_D0CH1-PadT9)") (class "Default")
      (node (ref "U1") (pin "T9") (pinfunction "VCCHRX1_D0CH1_T9") (pintype "power_in+no_connect"))
    )
    (net (code "16") (name "unconnected-(U1F-VCCHRX1_D1CH1-PadT13)") (class "Default")
      (node (ref "U1") (pin "T13") (pinfunction "VCCHRX1_D1CH1_T13") (pintype "power_in+no_connect"))
    )
    (net (code "17") (name "unconnected-(U1F-VCCIO0-PadF9)") (class "Default")
      (node (ref "U1") (pin "F9") (pinfunction "VCCIO0_F9") (pintype "power_in"))
    )
    (net (code "18") (name "unconnected-(U1F-VCCIO0-PadF10)") (class "Default")
      (node (ref "U1") (pin "F10") (pinfunction "VCCIO0_F10") (pintype "power_in"))
    )
    (net (code "19") (name "unconnected-(U1F-VCCIO1-PadF11)") (class "Default")
      (node (ref "U1") (pin "F11") (pinfunction "VCCIO1_F11") (pintype "power_in"))
    )
    (net (code "20") (name "unconnected-(U1F-VCCIO1-PadF12)") (class "Default")
      (node (ref "U1") (pin "F12") (pinfunction "VCCIO1_F12") (pintype "power_in"))
    )
    (net (code "21") (name "unconnected-(U1F-VCCIO2-PadH14)") (class "Default")
      (node (ref "U1") (pin "H14") (pinfunction "VCCIO2_H14") (pintype "power_in"))
    )
    (net (code "22") (name "unconnected-(U1F-VCCIO2-PadH15)") (class "Default")
      (node (ref "U1") (pin "H15") (pinfunction "VCCIO2_H15") (pintype "power_in"))
    )
    (net (code "23") (name "unconnected-(U1F-VCCIO2-PadJ15)") (class "Default")
      (node (ref "U1") (pin "J15") (pinfunction "VCCIO2_J15") (pintype "power_in"))
    )
    (net (code "24") (name "unconnected-(U1F-VCCIO3-PadL14)") (class "Default")
      (node (ref "U1") (pin "L14") (pinfunction "VCCIO3_L14") (pintype "power_in"))
    )
    (net (code "25") (name "unconnected-(U1F-VCCIO3-PadL15)") (class "Default")
      (node (ref "U1") (pin "L15") (pinfunction "VCCIO3_L15") (pintype "power_in"))
    )
    (net (code "26") (name "unconnected-(U1F-VCCIO3-PadM15)") (class "Default")
      (node (ref "U1") (pin "M15") (pinfunction "VCCIO3_M15") (pintype "power_in"))
    )
    (net (code "27") (name "unconnected-(U1F-VCCIO6-PadL6)") (class "Default")
      (node (ref "U1") (pin "L6") (pinfunction "VCCIO6_L6") (pintype "power_in"))
    )
    (net (code "28") (name "unconnected-(U1F-VCCIO6-PadL7)") (class "Default")
      (node (ref "U1") (pin "L7") (pinfunction "VCCIO6_L7") (pintype "power_in"))
    )
    (net (code "29") (name "unconnected-(U1F-VCCIO6-PadM6)") (class "Default")
      (node (ref "U1") (pin "M6") (pinfunction "VCCIO6_M6") (pintype "power_in"))
    )
    (net (code "30") (name "unconnected-(U1F-VCCIO7-PadH6)") (class "Default")
      (node (ref "U1") (pin "H6") (pinfunction "VCCIO7_H6") (pintype "power_in"))
    )
    (net (code "31") (name "unconnected-(U1F-VCCIO7-PadH7)") (class "Default")
      (node (ref "U1") (pin "H7") (pinfunction "VCCIO7_H7") (pintype "power_in"))
    )
    (net (code "32") (name "unconnected-(U1F-VCCIO7-PadJ6)") (class "Default")
      (node (ref "U1") (pin "J6") (pinfunction "VCCIO7_J6") (pintype "power_in"))
    )
  )
)
